# CH572D-R0.net
KiCad netlist of a schematic drawn in Altium Designer
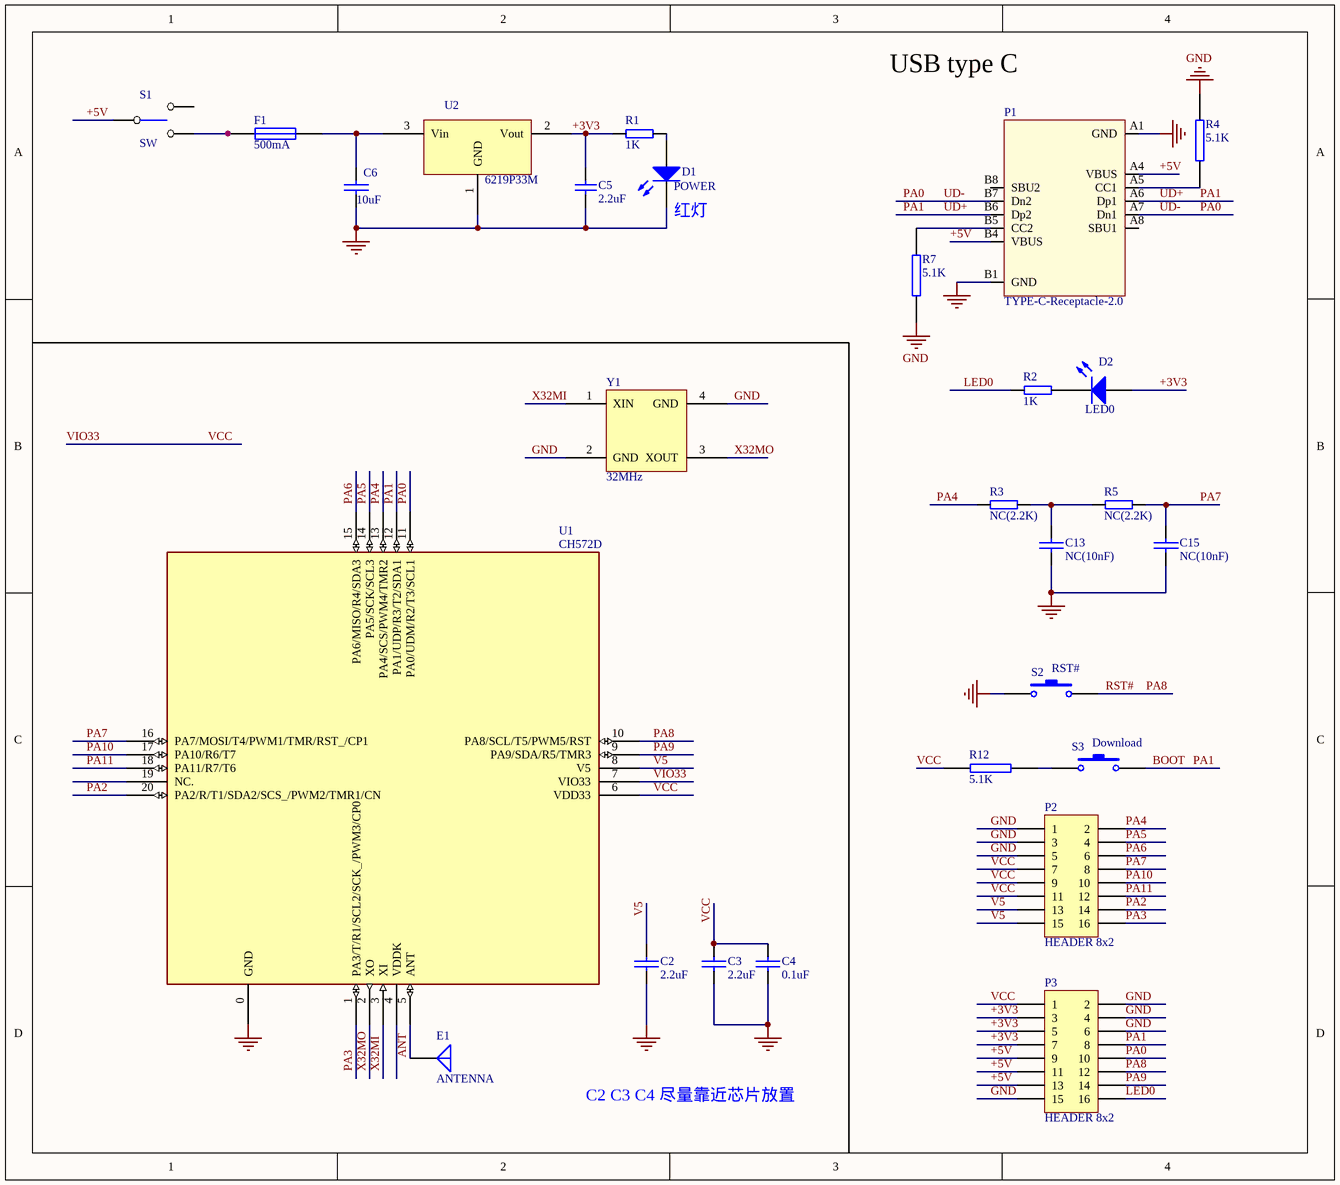
[diagram p0: CH572D-R0.SchDoc]

(export (version "E")
  (design (tool "Eeschema 10.0.6"))
  (components
    (comp (ref "C2")
      (value "2.2uF")
      (footprint "0402_C")
      (description "Capacitor")
      (libsource (lib "*") (part "CAP"))
    )
    (comp (ref "C3")
      (value "2.2uF")
      (footprint "0402_C")
      (description "Capacitor")
      (libsource (lib "*") (part "CAP"))
    )
    (comp (ref "C4")
      (value "0.1uF")
      (footprint "0402_C")
      (description "Capacitor")
      (libsource (lib "*") (part "CAP"))
    )
    (comp (ref "C5")
      (value "2.2uF")
      (footprint "0402_C")
      (description "Capacitor")
      (fields (field (name "PUBLISHER") "Altium Limited"))
      (libsource (lib "Miscellaneous Devices") (part "Cap"))
    )
    (comp (ref "C6")
      (value "10uF")
      (footprint "0603_C")
      (description "Capacitor")
      (libsource (lib "*") (part "CAP"))
    )
    (comp (ref "C13")
      (value "NC(10nF)")
      (footprint "0402_C")
      (description "Capacitor")
      (libsource (lib "*") (part "CAP"))
    )
    (comp (ref "C15")
      (value "NC(10nF)")
      (footprint "0402_C")
      (description "Capacitor")
      (libsource (lib "*") (part "CAP"))
    )
    (comp (ref "D1")
      (value "POWER")
      (footprint "0603+")
      (description "Typical INFRARED GaAs LED")
      (fields (field (name "PUBLISHER") "Altium Limited"))
      (libsource (lib "Miscellaneous Devices") (part "LED0"))
    )
    (comp (ref "D2")
      (value "LED0")
      (footprint "0603+")
      (description "Typical INFRARED GaAs LED")
      (fields (field (name "PUBLISHER") "Altium Limited"))
      (libsource (lib "") (part "LED0_1"))
    )
    (comp (ref "E1")
      (value "ANTENNA")
      (footprint "ANT-F-1-2.4G-1.6mmFR4")
      (description "Generic Antenna")
      (libsource (lib "*") (part "ANTENNA"))
    )
    (comp (ref "F1")
      (value "500mA")
      (footprint "0603")
      (description "Fuse")
      (libsource (lib "*") (part "FUSE1"))
    )
    (comp (ref "P1")
      (value "TYPE-C-Receptacle-2.0")
      (footprint "TYPE-C-Receptacle-2.0")
      (description "Type-C USB2.0 母座")
      (libsource (lib "Miscellaneous SCH Lib") (part "TYPE-C-Receptacle-2.0"))
    )
    (comp (ref "P2")
      (value "HEADER 8x2")
      (footprint "MYPCB:IDC16-2.54mm")
      (description "Header, 8-Pin, Dual row")
      (libsource (lib "wch_sch_others") (part "HEADER 8x2"))
    )
    (comp (ref "P3")
      (value "HEADER 8x2")
      (footprint "MYPCB:IDC16-2.54mm")
      (description "Header, 8-Pin, Dual row")
      (libsource (lib "wch_sch_others") (part "HEADER 8x2"))
    )
    (comp (ref "R1") (value "1K") (footprint "0402") (libsource (lib "wch_sch_others") (part "RES")))
    (comp (ref "R2") (value "1K") (footprint "0402") (libsource (lib "wch_sch_others") (part "RES")))
    (comp (ref "R3") (value "NC(2.2K)") (footprint "0402") (libsource (lib "wch_sch_others") (part "RES")))
    (comp (ref "R4") (value "5.1K") (footprint "0402") (libsource (lib "*") (part "RES2")))
    (comp (ref "R5") (value "NC(2.2K)") (footprint "0402") (libsource (lib "wch_sch_others") (part "RES")))
    (comp (ref "R7") (value "5.1K") (footprint "0402") (libsource (lib "*") (part "RES2")))
    (comp (ref "R12") (value "5.1K") (footprint "0402") (libsource (lib "*") (part "RES2")))
    (comp (ref "S1") (value "SW") (footprint "SW1") (libsource (lib "MYSCH") (part "SW")))
    (comp (ref "S2")
      (value "RST#")
      (footprint "SMD_6.1x3.65x2.5mm-KEY")
      (description "Switch")
      (fields (field (name "PUBLISHER") "Altium Limited"))
      (libsource (lib "*") (part "SW-PB"))
    )
    (comp (ref "S3")
      (value "Download")
      (footprint "SMD_6.1x3.65x2.5mm-KEY")
      (description "Switch")
      (fields (field (name "PUBLISHER") "Altium Limited"))
      (libsource (lib "*") (part "SW-PB"))
    )
    (comp (ref "U1")
      (value "CH572D")
      (footprint "QFN20_3X3")
      (description "RISC-V MCU with BLE/2.4GHz Wireless/USB/SPI/UART/I2C/PWM/CMP")
      (libsource (lib "DHXXXSCHd") (part "CH572D"))
    )
    (comp (ref "U2")
      (value "6219P33M")
      (footprint "SOT-23")
      (libsource (lib "wch_sch_others") (part "6219P33M"))
    )
    (comp (ref "Y1") (value "32MHz") (footprint "XT3225") (libsource (lib "wch_sch_others") (part "晶体")))
  )
  (nets
    (net (code "1") (name "/+3V3") (class "Default")
      (node (ref "C5") (pin "2") (pinfunction "2_2") (pintype "passive"))
      (node (ref "D2") (pin "1") (pinfunction "A_1") (pintype "passive"))
      (node (ref "P3") (pin "3") (pinfunction "3_3") (pintype "passive"))
      (node (ref "P3") (pin "5") (pinfunction "5_5") (pintype "passive"))
      (node (ref "P3") (pin "7") (pinfunction "7_7") (pintype "passive"))
      (node (ref "R1") (pin "2") (pintype "passive"))
      (node (ref "U2") (pin "2") (pinfunction "Vout_2") (pintype "passive"))
    )
    (net (code "2") (name "/+5V") (class "Default")
      (node (ref "P1") (pin "A4") (pinfunction "VBUS_A4") (pintype "passive"))
      (node (ref "P1") (pin "B4") (pinfunction "VBUS_B4") (pintype "passive"))
      (node (ref "P3") (pin "11") (pinfunction "11_11") (pintype "passive"))
      (node (ref "P3") (pin "13") (pinfunction "13_13") (pintype "passive"))
      (node (ref "P3") (pin "9") (pinfunction "9_9") (pintype "passive"))
      (node (ref "S1") (pin "1") (pinfunction "1_1") (pintype "passive"))
    )
    (net (code "3") (name "/ANT") (class "Default")
      (node (ref "E1") (pin "1") (pinfunction "A_1") (pintype "passive"))
      (node (ref "U1") (pin "5") (pinfunction "ANT_5") (pintype "bidirectional"))
    )
    (net (code "4") (name "/BOOT") (class "Default")
      (node (ref "P1") (pin "A6") (pinfunction "Dp1_A6") (pintype "passive"))
      (node (ref "P1") (pin "B6") (pinfunction "Dp2_B6") (pintype "passive"))
      (node (ref "P3") (pin "8") (pinfunction "8_8") (pintype "passive"))
      (node (ref "S3") (pin "2") (pinfunction "2_2") (pintype "passive"))
      (node (ref "U1") (pin "12") (pinfunction "PA1/UDP/R3/T2/SDA1_12") (pintype "bidirectional"))
    )
    (net (code "5") (name "/LED0") (class "Default")
      (node (ref "P3") (pin "16") (pinfunction "16_16") (pintype "passive"))
      (node (ref "R2") (pin "1") (pintype "passive"))
    )
    (net (code "6") (name "/PA0") (class "Default")
      (node (ref "P1") (pin "A7") (pinfunction "Dn1_A7") (pintype "passive"))
      (node (ref "P1") (pin "B7") (pinfunction "Dn2_B7") (pintype "passive"))
      (node (ref "P3") (pin "10") (pinfunction "10_10") (pintype "passive"))
      (node (ref "U1") (pin "11") (pinfunction "PA0/UDM/R2/T3/SCL1_11") (pintype "bidirectional"))
    )
    (net (code "7") (name "/PA2") (class "Default")
      (node (ref "P2") (pin "14") (pinfunction "14_14") (pintype "passive"))
      (node (ref "U1") (pin "20") (pinfunction "PA2/R/T1/SDA2/SCS_/PWM2/TMR1/CN_20") (pintype "bidirectional"))
    )
    (net (code "8") (name "/PA3") (class "Default")
      (node (ref "P2") (pin "16") (pinfunction "16_16") (pintype "passive"))
      (node (ref "U1") (pin "1") (pinfunction "PA3/T/R1/SCL2/SCK_/PWM3/CP0_1") (pintype "bidirectional"))
    )
    (net (code "9") (name "/PA4") (class "Default")
      (node (ref "P2") (pin "2") (pinfunction "2_2") (pintype "passive"))
      (node (ref "R3") (pin "1") (pintype "passive"))
      (node (ref "U1") (pin "13") (pinfunction "PA4/SCS/PWM4/TMR2_13") (pintype "bidirectional"))
    )
    (net (code "10") (name "/PA5") (class "Default")
      (node (ref "P2") (pin "4") (pinfunction "4_4") (pintype "passive"))
      (node (ref "U1") (pin "14") (pinfunction "PA5/SCK/SCL3_14") (pintype "bidirectional"))
    )
    (net (code "11") (name "/PA6") (class "Default")
      (node (ref "P2") (pin "6") (pinfunction "6_6") (pintype "passive"))
      (node (ref "U1") (pin "15") (pinfunction "PA6/MISO/R4/SDA3_15") (pintype "bidirectional"))
    )
    (net (code "12") (name "/PA7") (class "Default")
      (node (ref "C15") (pin "1") (pinfunction "1_1") (pintype "passive"))
      (node (ref "P2") (pin "8") (pinfunction "8_8") (pintype "passive"))
      (node (ref "R5") (pin "2") (pintype "passive"))
      (node (ref "U1") (pin "16") (pinfunction "PA7/MOSI/T4/PWM1/TMR/RST_/CP1_16") (pintype "bidirectional"))
    )
    (net (code "13") (name "/PA8") (class "Default")
      (node (ref "P3") (pin "12") (pinfunction "12_12") (pintype "passive"))
      (node (ref "S2") (pin "2") (pinfunction "2_2") (pintype "passive"))
      (node (ref "U1") (pin "10") (pinfunction "PA8/SCL/T5/PWM5/RST_10") (pintype "bidirectional"))
    )
    (net (code "14") (name "/PA9") (class "Default")
      (node (ref "P3") (pin "14") (pinfunction "14_14") (pintype "passive"))
      (node (ref "U1") (pin "9") (pinfunction "PA9/SDA/R5/TMR3_9") (pintype "bidirectional"))
    )
    (net (code "15") (name "/PA10") (class "Default")
      (node (ref "P2") (pin "10") (pinfunction "10_10") (pintype "passive"))
      (node (ref "U1") (pin "17") (pinfunction "PA10/R6/T7_17") (pintype "bidirectional"))
    )
    (net (code "16") (name "/PA11") (class "Default")
      (node (ref "P2") (pin "12") (pinfunction "12_12") (pintype "passive"))
      (node (ref "U1") (pin "18") (pinfunction "PA11/R7/T6_18") (pintype "bidirectional"))
    )
    (net (code "17") (name "/V5") (class "Default")
      (node (ref "C2") (pin "1") (pinfunction "1_1") (pintype "passive"))
      (node (ref "P2") (pin "13") (pinfunction "13_13") (pintype "passive"))
      (node (ref "P2") (pin "15") (pinfunction "15_15") (pintype "passive"))
      (node (ref "U1") (pin "8") (pinfunction "V5_8") (pintype "power_in"))
    )
    (net (code "18") (name "/VCC") (class "Default")
      (node (ref "C3") (pin "1") (pinfunction "1_1") (pintype "passive"))
      (node (ref "C4") (pin "1") (pinfunction "1_1") (pintype "passive"))
      (node (ref "P2") (pin "11") (pinfunction "11_11") (pintype "passive"))
      (node (ref "P2") (pin "7") (pinfunction "7_7") (pintype "passive"))
      (node (ref "P2") (pin "9") (pinfunction "9_9") (pintype "passive"))
      (node (ref "P3") (pin "1") (pinfunction "1_1") (pintype "passive"))
      (node (ref "R12") (pin "2") (pinfunction "2_2") (pintype "passive"))
      (node (ref "U1") (pin "6") (pinfunction "VDD33_6") (pintype "power_in"))
      (node (ref "U1") (pin "7") (pinfunction "VIO33_7") (pintype "power_in"))
    )
    (net (code "19") (name "/X32MI") (class "Default")
      (node (ref "U1") (pin "3") (pinfunction "XI_3") (pintype "input"))
      (node (ref "Y1") (pin "1") (pinfunction "XIN_1") (pintype "passive"))
    )
    (net (code "20") (name "/X32MO") (class "Default")
      (node (ref "U1") (pin "2") (pinfunction "XO_2") (pintype "output"))
      (node (ref "Y1") (pin "3") (pinfunction "XOUT_3") (pintype "passive"))
    )
    (net (code "21") (name "GND") (class "Default")
      (node (ref "C13") (pin "2") (pinfunction "2_2") (pintype "passive"))
      (node (ref "C15") (pin "2") (pinfunction "2_2") (pintype "passive"))
      (node (ref "C2") (pin "2") (pinfunction "2_2") (pintype "passive"))
      (node (ref "C3") (pin "2") (pinfunction "2_2") (pintype "passive"))
      (node (ref "C4") (pin "2") (pinfunction "2_2") (pintype "passive"))
      (node (ref "C5") (pin "1") (pinfunction "1_1") (pintype "passive"))
      (node (ref "C6") (pin "2") (pinfunction "2_2") (pintype "passive"))
      (node (ref "D1") (pin "2") (pinfunction "K_2") (pintype "passive"))
      (node (ref "P1") (pin "A1") (pinfunction "GND_A1") (pintype "passive"))
      (node (ref "P1") (pin "B1") (pinfunction "GND_B1") (pintype "passive"))
      (node (ref "P2") (pin "1") (pinfunction "1_1") (pintype "passive"))
      (node (ref "P2") (pin "3") (pinfunction "3_3") (pintype "passive"))
      (node (ref "P2") (pin "5") (pinfunction "5_5") (pintype "passive"))
      (node (ref "P3") (pin "15") (pinfunction "15_15") (pintype "passive"))
      (node (ref "P3") (pin "2") (pinfunction "2_2") (pintype "passive"))
      (node (ref "P3") (pin "4") (pinfunction "4_4") (pintype "passive"))
      (node (ref "P3") (pin "6") (pinfunction "6_6") (pintype "passive"))
      (node (ref "R4") (pin "2") (pinfunction "2_2") (pintype "passive"))
      (node (ref "R7") (pin "1") (pinfunction "1_1") (pintype "passive"))
      (node (ref "S2") (pin "1") (pinfunction "1_1") (pintype "passive"))
      (node (ref "U1") (pin "0") (pinfunction "GND_0") (pintype "power_in"))
      (node (ref "U2") (pin "1") (pinfunction "GND_1") (pintype "passive"))
      (node (ref "Y1") (pin "2") (pinfunction "GND_2") (pintype "passive"))
      (node (ref "Y1") (pin "4") (pinfunction "GND_4") (pintype "passive"))
    )
    (net (code "22") (name "Net-(C13-Pad1)") (class "Default")
      (node (ref "C13") (pin "1") (pinfunction "1_1") (pintype "passive"))
      (node (ref "R3") (pin "2") (pintype "passive"))
      (node (ref "R5") (pin "1") (pintype "passive"))
    )
    (net (code "23") (name "Net-(D1-A)") (class "Default")
      (node (ref "D1") (pin "1") (pinfunction "A_1") (pintype "passive"))
      (node (ref "R1") (pin "1") (pintype "passive"))
    )
    (net (code "24") (name "Net-(D2-K)") (class "Default")
      (node (ref "D2") (pin "2") (pinfunction "K_2") (pintype "passive"))
      (node (ref "R2") (pin "2") (pintype "passive"))
    )
    (net (code "25") (name "Net-(F1-Pad1)") (class "Default")
      (node (ref "F1") (pin "1") (pinfunction "1_1") (pintype "passive"))
      (node (ref "S1") (pin "2") (pinfunction "2_2") (pintype "passive"))
    )
    (net (code "26") (name "Net-(P1-CC1)") (class "Default")
      (node (ref "P1") (pin "A5") (pinfunction "CC1_A5") (pintype "passive"))
      (node (ref "R4") (pin "1") (pinfunction "1_1") (pintype "passive"))
    )
    (net (code "27") (name "Net-(P1-CC2)") (class "Default")
      (node (ref "P1") (pin "B5") (pinfunction "CC2_B5") (pintype "passive"))
      (node (ref "R7") (pin "2") (pinfunction "2_2") (pintype "passive"))
    )
    (net (code "28") (name "Net-(R12-Pad1)") (class "Default")
      (node (ref "R12") (pin "1") (pinfunction "1_1") (pintype "passive"))
      (node (ref "S3") (pin "1") (pinfunction "1_1") (pintype "passive"))
    )
    (net (code "29") (name "Net-(U2-Vin)") (class "Default")
      (node (ref "C6") (pin "1") (pinfunction "1_1") (pintype "passive"))
      (node (ref "F1") (pin "2") (pinfunction "2_2") (pintype "passive"))
      (node (ref "U2") (pin "3") (pinfunction "Vin_3") (pintype "passive"))
    )
    (net (code "30") (name "unconnected-(P1-SBU1-PadA8)") (class "Default")
      (node (ref "P1") (pin "A8") (pinfunction "SBU1_A8") (pintype "passive"))
    )
    (net (code "31") (name "unconnected-(P1-SBU2-PadB8)") (class "Default")
      (node (ref "P1") (pin "B8") (pinfunction "SBU2_B8") (pintype "passive"))
    )
    (net (code "32") (name "unconnected-(S1-Pad3)") (class "Default")
      (node (ref "S1") (pin "3") (pinfunction "3_3") (pintype "passive"))
    )
    (net (code "33") (name "unconnected-(U1-NC.-Pad19)") (class "Default")
      (node (ref "U1") (pin "19") (pinfunction "NC._19") (pintype "passive"))
    )
    (net (code "34") (name "unconnected-(U1-VDDK-Pad4)") (class "Default")
      (node (ref "U1") (pin "4") (pinfunction "VDDK_4") (pintype "power_in"))
    )
  )
)
